# qudong.net
KiCad netlist of a schematic drawn in Altium Designer
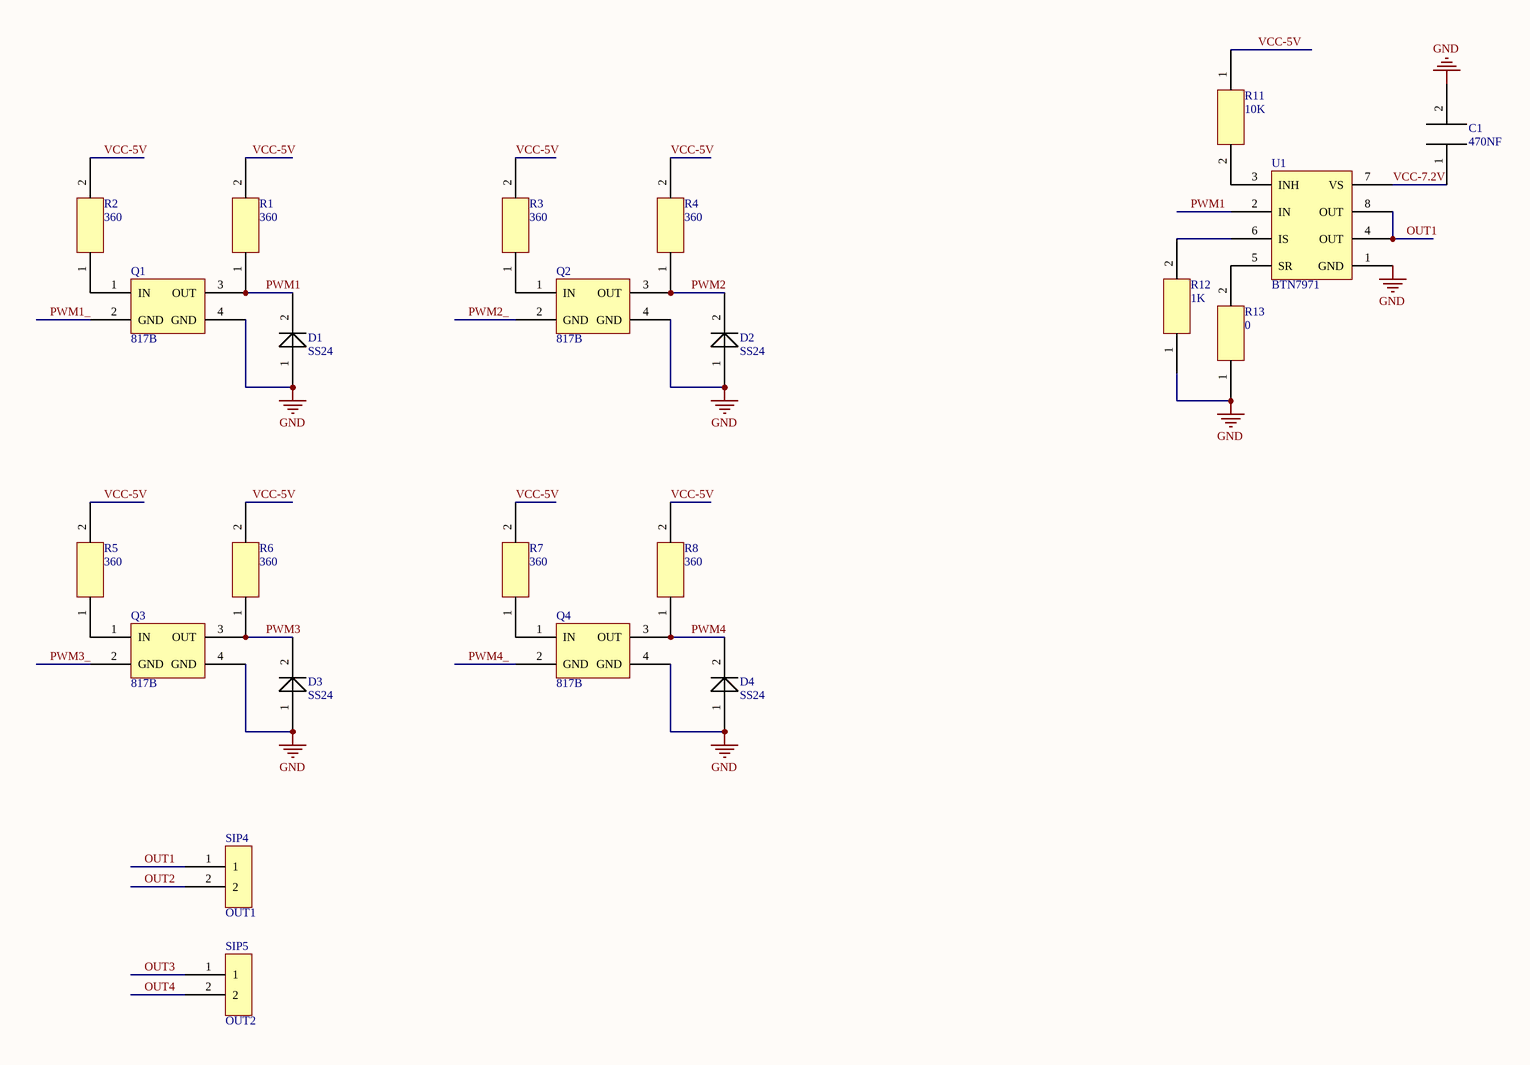
[diagram p0: qudong.SchDoc, left]
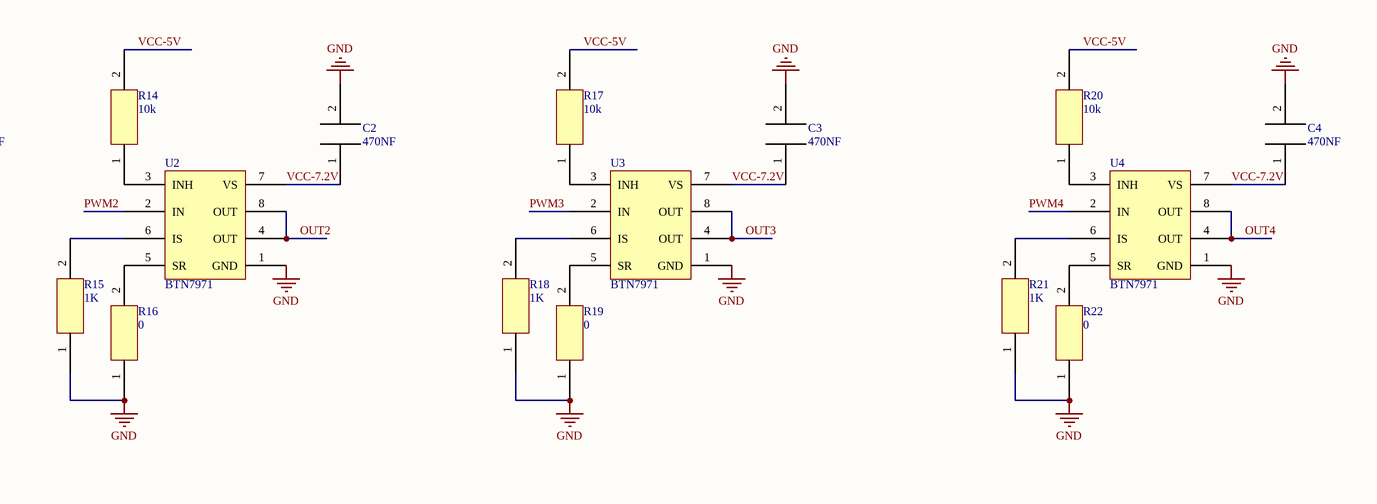
[diagram p1: qudong.SchDoc, right]

(export (version "E")
  (design (tool "Eeschema 10.0.6"))
  (components
    (comp (ref "C1") (value "470NF") (footprint "CAP-T") (libsource (lib "qudong") (part "CAP-T")))
    (comp (ref "C2") (value "470NF") (footprint "CAP-T") (libsource (lib "qudong") (part "CAP-T")))
    (comp (ref "C3") (value "470NF") (footprint "CAP-T") (libsource (lib "qudong") (part "CAP-T")))
    (comp (ref "C4") (value "470NF") (footprint "CAP-T") (libsource (lib "qudong") (part "CAP-T")))
    (comp (ref "D1") (value "SS24") (footprint "SS24") (libsource (lib "qudong") (part "SS24")))
    (comp (ref "D2") (value "SS24") (footprint "SS24") (libsource (lib "qudong") (part "SS24")))
    (comp (ref "D3") (value "SS24") (footprint "SS24") (libsource (lib "qudong") (part "SS24")))
    (comp (ref "D4") (value "SS24") (footprint "SS24") (libsource (lib "qudong") (part "SS24")))
    (comp (ref "Q1") (value "817B") (footprint "817B") (libsource (lib "qudong") (part "817B")))
    (comp (ref "Q2") (value "817B") (footprint "817B") (libsource (lib "qudong") (part "817B")))
    (comp (ref "Q3") (value "817B") (footprint "817B") (libsource (lib "qudong") (part "817B")))
    (comp (ref "Q4") (value "817B") (footprint "817B") (libsource (lib "qudong") (part "817B")))
    (comp (ref "R1") (value "360") (footprint "RES-T") (libsource (lib "qudong") (part "RES-T")))
    (comp (ref "R2") (value "360") (footprint "RES-T") (libsource (lib "qudong") (part "RES-T")))
    (comp (ref "R3") (value "360") (footprint "RES-T") (libsource (lib "qudong") (part "RES-T")))
    (comp (ref "R4") (value "360") (footprint "RES-T") (libsource (lib "qudong") (part "RES-T")))
    (comp (ref "R5") (value "360") (footprint "RES-T") (libsource (lib "qudong") (part "RES-T")))
    (comp (ref "R6") (value "360") (footprint "RES-T") (libsource (lib "qudong") (part "RES-T")))
    (comp (ref "R7") (value "360") (footprint "RES-T") (libsource (lib "qudong") (part "RES-T")))
    (comp (ref "R8") (value "360") (footprint "RES-T") (libsource (lib "qudong") (part "RES-T")))
    (comp (ref "R11") (value "10K") (footprint "RES-T") (libsource (lib "") (part "RES-T_1")))
    (comp (ref "R12") (value "1K") (footprint "RES-T") (libsource (lib "qudong") (part "RES-T")))
    (comp (ref "R13") (value "0") (footprint "RES-T") (libsource (lib "qudong") (part "RES-T")))
    (comp (ref "R14") (value "10k") (footprint "RES-T") (libsource (lib "qudong") (part "RES-T")))
    (comp (ref "R15") (value "1K") (footprint "RES-T") (libsource (lib "qudong") (part "RES-T")))
    (comp (ref "R16") (value "0") (footprint "RES-T") (libsource (lib "qudong") (part "RES-T")))
    (comp (ref "R17") (value "10k") (footprint "RES-T") (libsource (lib "qudong") (part "RES-T")))
    (comp (ref "R18") (value "1K") (footprint "RES-T") (libsource (lib "qudong") (part "RES-T")))
    (comp (ref "R19") (value "0") (footprint "RES-T") (libsource (lib "qudong") (part "RES-T")))
    (comp (ref "R20") (value "10k") (footprint "RES-T") (libsource (lib "qudong") (part "RES-T")))
    (comp (ref "R21") (value "1K") (footprint "RES-T") (libsource (lib "qudong") (part "RES-T")))
    (comp (ref "R22") (value "0") (footprint "RES-T") (libsource (lib "qudong") (part "RES-T")))
    (comp (ref "SIP4") (value "OUT1") (footprint "SIP2-3MM") (libsource (lib "qudong") (part "SIP2")))
    (comp (ref "SIP5") (value "OUT2") (footprint "SIP2-3MM") (libsource (lib "qudong") (part "SIP2")))
    (comp (ref "U1") (value "BTN7971") (footprint "BTN7971") (libsource (lib "qudong") (part "BTN7971")))
    (comp (ref "U2") (value "BTN7971") (footprint "BTN7971") (libsource (lib "qudong") (part "BTN7971")))
    (comp (ref "U3") (value "BTN7971") (footprint "BTN7971") (libsource (lib "qudong") (part "BTN7971")))
    (comp (ref "U4") (value "BTN7971") (footprint "BTN7971") (libsource (lib "qudong") (part "BTN7971")))
  )
  (nets
    (net (code "1") (name "/OUT1") (class "Default")
      (node (ref "SIP4") (pin "1") (pinfunction "1_1") (pintype "passive"))
      (node (ref "U1") (pin "4") (pinfunction "OUT_4") (pintype "passive"))
      (node (ref "U1") (pin "8") (pinfunction "OUT_8") (pintype "passive"))
    )
    (net (code "2") (name "/OUT2") (class "Default")
      (node (ref "SIP4") (pin "2") (pinfunction "2_2") (pintype "passive"))
      (node (ref "U2") (pin "4") (pinfunction "OUT_4") (pintype "passive"))
      (node (ref "U2") (pin "8") (pinfunction "OUT_8") (pintype "passive"))
    )
    (net (code "3") (name "/OUT3") (class "Default")
      (node (ref "SIP5") (pin "1") (pinfunction "1_1") (pintype "passive"))
      (node (ref "U3") (pin "4") (pinfunction "OUT_4") (pintype "passive"))
      (node (ref "U3") (pin "8") (pinfunction "OUT_8") (pintype "passive"))
    )
    (net (code "4") (name "/OUT4") (class "Default")
      (node (ref "SIP5") (pin "2") (pinfunction "2_2") (pintype "passive"))
      (node (ref "U4") (pin "4") (pinfunction "OUT_4") (pintype "passive"))
      (node (ref "U4") (pin "8") (pinfunction "OUT_8") (pintype "passive"))
    )
    (net (code "5") (name "/PWM1") (class "Default")
      (node (ref "D1") (pin "2") (pinfunction "2_2") (pintype "passive"))
      (node (ref "Q1") (pin "3") (pinfunction "OUT_3") (pintype "passive"))
      (node (ref "R1") (pin "1") (pinfunction "1_1") (pintype "passive"))
      (node (ref "U1") (pin "2") (pinfunction "IN_2") (pintype "passive"))
    )
    (net (code "6") (name "/PWM1_") (class "Default")
      (node (ref "Q1") (pin "2") (pinfunction "GND_2") (pintype "passive"))
    )
    (net (code "7") (name "/PWM2") (class "Default")
      (node (ref "D2") (pin "2") (pinfunction "2_2") (pintype "passive"))
      (node (ref "Q2") (pin "3") (pinfunction "OUT_3") (pintype "passive"))
      (node (ref "R4") (pin "1") (pinfunction "1_1") (pintype "passive"))
      (node (ref "U2") (pin "2") (pinfunction "IN_2") (pintype "passive"))
    )
    (net (code "8") (name "/PWM2_") (class "Default")
      (node (ref "Q2") (pin "2") (pinfunction "GND_2") (pintype "passive"))
    )
    (net (code "9") (name "/PWM3") (class "Default")
      (node (ref "D3") (pin "2") (pinfunction "2_2") (pintype "passive"))
      (node (ref "Q3") (pin "3") (pinfunction "OUT_3") (pintype "passive"))
      (node (ref "R6") (pin "1") (pinfunction "1_1") (pintype "passive"))
      (node (ref "U3") (pin "2") (pinfunction "IN_2") (pintype "passive"))
    )
    (net (code "10") (name "/PWM3_") (class "Default")
      (node (ref "Q3") (pin "2") (pinfunction "GND_2") (pintype "passive"))
    )
    (net (code "11") (name "/PWM4") (class "Default")
      (node (ref "D4") (pin "2") (pinfunction "2_2") (pintype "passive"))
      (node (ref "Q4") (pin "3") (pinfunction "OUT_3") (pintype "passive"))
      (node (ref "R8") (pin "1") (pinfunction "1_1") (pintype "passive"))
      (node (ref "U4") (pin "2") (pinfunction "IN_2") (pintype "passive"))
    )
    (net (code "12") (name "/PWM4_") (class "Default")
      (node (ref "Q4") (pin "2") (pinfunction "GND_2") (pintype "passive"))
    )
    (net (code "13") (name "/VCC-5V") (class "Default")
      (node (ref "R1") (pin "2") (pinfunction "2_2") (pintype "passive"))
      (node (ref "R11") (pin "1") (pinfunction "1_1") (pintype "passive"))
      (node (ref "R14") (pin "2") (pinfunction "2_2") (pintype "passive"))
      (node (ref "R17") (pin "2") (pinfunction "2_2") (pintype "passive"))
      (node (ref "R2") (pin "2") (pinfunction "2_2") (pintype "passive"))
      (node (ref "R20") (pin "2") (pinfunction "2_2") (pintype "passive"))
      (node (ref "R3") (pin "2") (pinfunction "2_2") (pintype "passive"))
      (node (ref "R4") (pin "2") (pinfunction "2_2") (pintype "passive"))
      (node (ref "R5") (pin "2") (pinfunction "2_2") (pintype "passive"))
      (node (ref "R6") (pin "2") (pinfunction "2_2") (pintype "passive"))
      (node (ref "R7") (pin "2") (pinfunction "2_2") (pintype "passive"))
      (node (ref "R8") (pin "2") (pinfunction "2_2") (pintype "passive"))
    )
    (net (code "14") (name "/VCC-7.2V") (class "Default")
      (node (ref "C1") (pin "1") (pinfunction "1_1") (pintype "passive"))
      (node (ref "C2") (pin "1") (pinfunction "1_1") (pintype "passive"))
      (node (ref "C3") (pin "1") (pinfunction "1_1") (pintype "passive"))
      (node (ref "C4") (pin "1") (pinfunction "1_1") (pintype "passive"))
      (node (ref "U1") (pin "7") (pinfunction "VS_7") (pintype "passive"))
      (node (ref "U2") (pin "7") (pinfunction "VS_7") (pintype "passive"))
      (node (ref "U3") (pin "7") (pinfunction "VS_7") (pintype "passive"))
      (node (ref "U4") (pin "7") (pinfunction "VS_7") (pintype "passive"))
    )
    (net (code "15") (name "GND") (class "Default")
      (node (ref "C1") (pin "2") (pinfunction "2_2") (pintype "passive"))
      (node (ref "C2") (pin "2") (pinfunction "2_2") (pintype "passive"))
      (node (ref "C3") (pin "2") (pinfunction "2_2") (pintype "passive"))
      (node (ref "C4") (pin "2") (pinfunction "2_2") (pintype "passive"))
      (node (ref "D1") (pin "1") (pinfunction "1_1") (pintype "passive"))
      (node (ref "D2") (pin "1") (pinfunction "1_1") (pintype "passive"))
      (node (ref "D3") (pin "1") (pinfunction "1_1") (pintype "passive"))
      (node (ref "D4") (pin "1") (pinfunction "1_1") (pintype "passive"))
      (node (ref "Q1") (pin "4") (pinfunction "GND_4") (pintype "passive"))
      (node (ref "Q2") (pin "4") (pinfunction "GND_4") (pintype "passive"))
      (node (ref "Q3") (pin "4") (pinfunction "GND_4") (pintype "passive"))
      (node (ref "Q4") (pin "4") (pinfunction "GND_4") (pintype "passive"))
      (node (ref "R12") (pin "1") (pinfunction "1_1") (pintype "passive"))
      (node (ref "R13") (pin "1") (pinfunction "1_1") (pintype "passive"))
      (node (ref "R15") (pin "1") (pinfunction "1_1") (pintype "passive"))
      (node (ref "R16") (pin "1") (pinfunction "1_1") (pintype "passive"))
      (node (ref "R18") (pin "1") (pinfunction "1_1") (pintype "passive"))
      (node (ref "R19") (pin "1") (pinfunction "1_1") (pintype "passive"))
      (node (ref "R21") (pin "1") (pinfunction "1_1") (pintype "passive"))
      (node (ref "R22") (pin "1") (pinfunction "1_1") (pintype "passive"))
      (node (ref "U1") (pin "1") (pinfunction "GND_1") (pintype "passive"))
      (node (ref "U2") (pin "1") (pinfunction "GND_1") (pintype "passive"))
      (node (ref "U3") (pin "1") (pinfunction "GND_1") (pintype "passive"))
      (node (ref "U4") (pin "1") (pinfunction "GND_1") (pintype "passive"))
    )
    (net (code "16") (name "Net-(Q1-IN)") (class "Default")
      (node (ref "Q1") (pin "1") (pinfunction "IN_1") (pintype "passive"))
      (node (ref "R2") (pin "1") (pinfunction "1_1") (pintype "passive"))
    )
    (net (code "17") (name "Net-(Q2-IN)") (class "Default")
      (node (ref "Q2") (pin "1") (pinfunction "IN_1") (pintype "passive"))
      (node (ref "R3") (pin "1") (pinfunction "1_1") (pintype "passive"))
    )
    (net (code "18") (name "Net-(Q3-IN)") (class "Default")
      (node (ref "Q3") (pin "1") (pinfunction "IN_1") (pintype "passive"))
      (node (ref "R5") (pin "1") (pinfunction "1_1") (pintype "passive"))
    )
    (net (code "19") (name "Net-(Q4-IN)") (class "Default")
      (node (ref "Q4") (pin "1") (pinfunction "IN_1") (pintype "passive"))
      (node (ref "R7") (pin "1") (pinfunction "1_1") (pintype "passive"))
    )
    (net (code "20") (name "Net-(U1-INH)") (class "Default")
      (node (ref "R11") (pin "2") (pinfunction "2_2") (pintype "passive"))
      (node (ref "U1") (pin "3") (pinfunction "INH_3") (pintype "passive"))
    )
    (net (code "21") (name "Net-(U1-IS)") (class "Default")
      (node (ref "R12") (pin "2") (pinfunction "2_2") (pintype "passive"))
      (node (ref "U1") (pin "6") (pinfunction "IS_6") (pintype "passive"))
    )
    (net (code "22") (name "Net-(U1-SR)") (class "Default")
      (node (ref "R13") (pin "2") (pinfunction "2_2") (pintype "passive"))
      (node (ref "U1") (pin "5") (pinfunction "SR_5") (pintype "passive"))
    )
    (net (code "23") (name "Net-(U2-INH)") (class "Default")
      (node (ref "R14") (pin "1") (pinfunction "1_1") (pintype "passive"))
      (node (ref "U2") (pin "3") (pinfunction "INH_3") (pintype "passive"))
    )
    (net (code "24") (name "Net-(U2-IS)") (class "Default")
      (node (ref "R15") (pin "2") (pinfunction "2_2") (pintype "passive"))
      (node (ref "U2") (pin "6") (pinfunction "IS_6") (pintype "passive"))
    )
    (net (code "25") (name "Net-(U2-SR)") (class "Default")
      (node (ref "R16") (pin "2") (pinfunction "2_2") (pintype "passive"))
      (node (ref "U2") (pin "5") (pinfunction "SR_5") (pintype "passive"))
    )
    (net (code "26") (name "Net-(U3-INH)") (class "Default")
      (node (ref "R17") (pin "1") (pinfunction "1_1") (pintype "passive"))
      (node (ref "U3") (pin "3") (pinfunction "INH_3") (pintype "passive"))
    )
    (net (code "27") (name "Net-(U3-IS)") (class "Default")
      (node (ref "R18") (pin "2") (pinfunction "2_2") (pintype "passive"))
      (node (ref "U3") (pin "6") (pinfunction "IS_6") (pintype "passive"))
    )
    (net (code "28") (name "Net-(U3-SR)") (class "Default")
      (node (ref "R19") (pin "2") (pinfunction "2_2") (pintype "passive"))
      (node (ref "U3") (pin "5") (pinfunction "SR_5") (pintype "passive"))
    )
    (net (code "29") (name "Net-(U4-INH)") (class "Default")
      (node (ref "R20") (pin "1") (pinfunction "1_1") (pintype "passive"))
      (node (ref "U4") (pin "3") (pinfunction "INH_3") (pintype "passive"))
    )
    (net (code "30") (name "Net-(U4-IS)") (class "Default")
      (node (ref "R21") (pin "2") (pinfunction "2_2") (pintype "passive"))
      (node (ref "U4") (pin "6") (pinfunction "IS_6") (pintype "passive"))
    )
    (net (code "31") (name "Net-(U4-SR)") (class "Default")
      (node (ref "R22") (pin "2") (pinfunction "2_2") (pintype "passive"))
      (node (ref "U4") (pin "5") (pinfunction "SR_5") (pintype "passive"))
    )
  )
)
